# LEDCube.net
KiCad netlist of a schematic drawn in Altium Designer
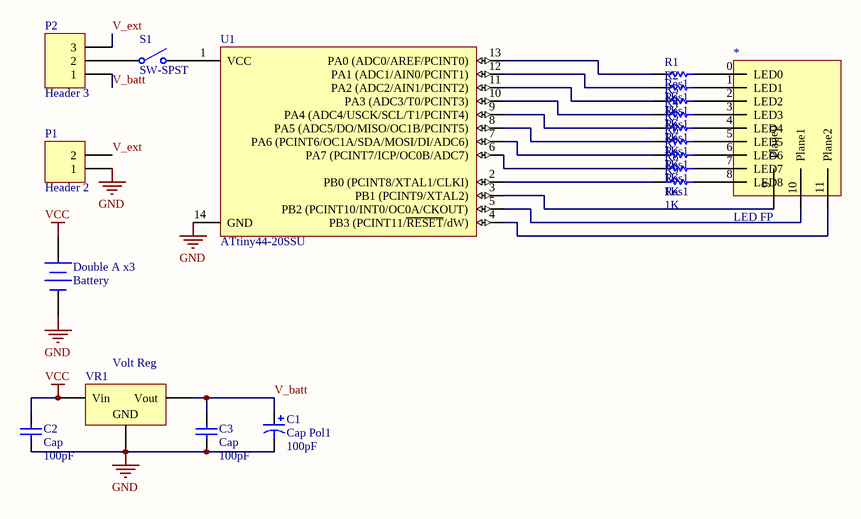
[diagram p0: LEDCube.SchDoc]

(export (version "E")
  (design (tool "Eeschema 10.0.6"))
  (components
    (comp (ref "*")
      (value "LED FP")
      (footprint "Cube Column FP")
      (libsource (lib "LEDFPSch") (part "LED FP"))
    )
    (comp (ref "C1")
      (value "Cap Pol1")
      (footprint "RB7.6-15")
      (description "Polarized Capacitor (Radial)")
      (fields (field (name "ALTIUM_VALUE") "100pF") (field (name "PUBLISHER") "Altium Limited"))
      (libsource (lib "Miscellaneous Devices") (part "Cap Pol1"))
    )
    (comp (ref "C2")
      (value "Cap")
      (footprint "RAD-0.3")
      (description "Capacitor")
      (fields (field (name "ALTIUM_VALUE") "100pF") (field (name "PUBLISHER") "Altium Limited"))
      (libsource (lib "Miscellaneous Devices") (part "Cap"))
    )
    (comp (ref "C3")
      (value "Cap")
      (footprint "RAD-0.3")
      (description "Capacitor")
      (fields (field (name "ALTIUM_VALUE") "100pF") (field (name "PUBLISHER") "Altium Limited"))
      (libsource (lib "Miscellaneous Devices") (part "Cap"))
    )
    (comp (ref "Double A x3")
      (value "Battery")
      (footprint "BAT-2")
      (description "Multicell Battery")
      (fields (field (name "PUBLISHER") "Altium Limited"))
      (libsource (lib "Miscellaneous Devices") (part "Battery"))
    )
    (comp (ref "P1")
      (value "Header 2")
      (footprint "HDR1X2")
      (description "Header, 2-Pin")
      (fields (field (name "PUBLISHER") "Altium Limited"))
      (libsource (lib "Miscellaneous Connectors") (part "Header 2"))
    )
    (comp (ref "P2")
      (value "Header 3")
      (footprint "HDR1X3")
      (description "Header, 3-Pin")
      (fields (field (name "PUBLISHER") "Altium Limited"))
      (libsource (lib "Miscellaneous Connectors") (part "Header 3"))
    )
    (comp (ref "R1")
      (value "Res1")
      (footprint "AXIAL-0.3")
      (description "Resistor")
      (fields (field (name "ALTIUM_VALUE") "1K") (field (name "PUBLISHER") "Altium Limited"))
      (libsource (lib "Miscellaneous Devices") (part "Res1"))
    )
    (comp (ref "R2")
      (value "Res1")
      (footprint "AXIAL-0.3")
      (description "Resistor")
      (fields (field (name "ALTIUM_VALUE") "1K") (field (name "PUBLISHER") "Altium Limited"))
      (libsource (lib "Miscellaneous Devices") (part "Res1"))
    )
    (comp (ref "R3")
      (value "Res1")
      (footprint "AXIAL-0.3")
      (description "Resistor")
      (fields (field (name "ALTIUM_VALUE") "1K") (field (name "PUBLISHER") "Altium Limited"))
      (libsource (lib "Miscellaneous Devices") (part "Res1"))
    )
    (comp (ref "R4")
      (value "Res1")
      (footprint "AXIAL-0.3")
      (description "Resistor")
      (fields (field (name "ALTIUM_VALUE") "1K") (field (name "PUBLISHER") "Altium Limited"))
      (libsource (lib "Miscellaneous Devices") (part "Res1"))
    )
    (comp (ref "R5")
      (value "Res1")
      (footprint "AXIAL-0.3")
      (description "Resistor")
      (fields (field (name "ALTIUM_VALUE") "1K") (field (name "PUBLISHER") "Altium Limited"))
      (libsource (lib "Miscellaneous Devices") (part "Res1"))
    )
    (comp (ref "R6")
      (value "Res1")
      (footprint "AXIAL-0.3")
      (description "Resistor")
      (fields (field (name "ALTIUM_VALUE") "1K") (field (name "PUBLISHER") "Altium Limited"))
      (libsource (lib "Miscellaneous Devices") (part "Res1"))
    )
    (comp (ref "R7")
      (value "Res1")
      (footprint "AXIAL-0.3")
      (description "Resistor")
      (fields (field (name "ALTIUM_VALUE") "1K") (field (name "PUBLISHER") "Altium Limited"))
      (libsource (lib "Miscellaneous Devices") (part "Res1"))
    )
    (comp (ref "R8")
      (value "Res1")
      (footprint "AXIAL-0.3")
      (description "Resistor")
      (fields (field (name "ALTIUM_VALUE") "1K") (field (name "PUBLISHER") "Altium Limited"))
      (libsource (lib "Miscellaneous Devices") (part "Res1"))
    )
    (comp (ref "R9")
      (value "Res1")
      (footprint "AXIAL-0.3")
      (description "Resistor")
      (fields (field (name "ALTIUM_VALUE") "1K") (field (name "PUBLISHER") "Altium Limited"))
      (libsource (lib "Miscellaneous Devices") (part "Res1"))
    )
    (comp (ref "S1")
      (value "SW-SPST")
      (footprint "SPST-2")
      (description "Single-Pole, Single-Throw Switch")
      (fields (field (name "PUBLISHER") "Altium Limited"))
      (libsource (lib "Miscellaneous Devices") (part "SW-SPST"))
    )
    (comp (ref "U1")
      (value "ATtiny44-20SSU")
      (footprint "14S1_N")
      (fields (field (name "PUBLISHER") "Altium Limited"))
      (libsource (lib "Atmel Microcontroller 8-Bit tinyAVR") (part "ATtiny44-20SSU"))
    )
    (comp (ref "VR1")
      (value "Volt Reg")
      (footprint "D2PAK_N")
      (description "Voltage Regulator")
      (fields (field (name "PUBLISHER") "Altium Limited"))
      (libsource (lib "Miscellaneous Devices") (part "Volt Reg"))
    )
  )
  (nets
    (net (code "1") (name "/V_batt") (class "Default")
      (node (ref "C1") (pin "1") (pinfunction "1_1") (pintype "passive"))
      (node (ref "C3") (pin "2") (pinfunction "2_2") (pintype "passive"))
      (node (ref "P2") (pin "1") (pinfunction "1_1") (pintype "passive"))
      (node (ref "VR1") (pin "3") (pinfunction "Vout_3") (pintype "passive"))
    )
    (net (code "2") (name "/V_ext") (class "Default")
      (node (ref "P1") (pin "2") (pinfunction "2_2") (pintype "passive"))
      (node (ref "P2") (pin "3") (pinfunction "3_3") (pintype "passive"))
    )
    (net (code "3") (name "GND") (class "Default")
      (node (ref "C1") (pin "2") (pinfunction "2_2") (pintype "passive"))
      (node (ref "C2") (pin "1") (pinfunction "1_1") (pintype "passive"))
      (node (ref "C3") (pin "1") (pinfunction "1_1") (pintype "passive"))
      (node (ref "Double A x3") (pin "2") (pinfunction "-_2") (pintype "passive"))
      (node (ref "P1") (pin "1") (pinfunction "1_1") (pintype "passive"))
      (node (ref "U1") (pin "14") (pinfunction "GND_14") (pintype "power_in"))
      (node (ref "VR1") (pin "2") (pinfunction "GND_2") (pintype "passive"))
    )
    (net (code "4") (name "Net-(*-LED0)") (class "Default")
      (node (ref "*") (pin "0") (pinfunction "LED0_0") (pintype "passive"))
      (node (ref "R1") (pin "2") (pinfunction "2_2") (pintype "passive"))
    )
    (net (code "5") (name "Net-(*-LED1)") (class "Default")
      (node (ref "*") (pin "1") (pinfunction "LED1_1") (pintype "passive"))
      (node (ref "R2") (pin "2") (pinfunction "2_2") (pintype "passive"))
    )
    (net (code "6") (name "Net-(*-LED2)") (class "Default")
      (node (ref "*") (pin "2") (pinfunction "LED2_2") (pintype "passive"))
      (node (ref "R3") (pin "2") (pinfunction "2_2") (pintype "passive"))
    )
    (net (code "7") (name "Net-(*-LED3)") (class "Default")
      (node (ref "*") (pin "3") (pinfunction "LED3_3") (pintype "passive"))
      (node (ref "R4") (pin "2") (pinfunction "2_2") (pintype "passive"))
    )
    (net (code "8") (name "Net-(*-LED4)") (class "Default")
      (node (ref "*") (pin "4") (pinfunction "LED4_4") (pintype "passive"))
      (node (ref "R5") (pin "2") (pinfunction "2_2") (pintype "passive"))
    )
    (net (code "9") (name "Net-(*-LED5)") (class "Default")
      (node (ref "*") (pin "5") (pinfunction "LED5_5") (pintype "passive"))
      (node (ref "R6") (pin "2") (pinfunction "2_2") (pintype "passive"))
    )
    (net (code "10") (name "Net-(*-LED6)") (class "Default")
      (node (ref "*") (pin "6") (pinfunction "LED6_6") (pintype "passive"))
      (node (ref "R7") (pin "2") (pinfunction "2_2") (pintype "passive"))
    )
    (net (code "11") (name "Net-(*-LED7)") (class "Default")
      (node (ref "*") (pin "7") (pinfunction "LED7_7") (pintype "passive"))
      (node (ref "R8") (pin "2") (pinfunction "2_2") (pintype "passive"))
    )
    (net (code "12") (name "Net-(*-LED8)") (class "Default")
      (node (ref "*") (pin "8") (pinfunction "LED8_8") (pintype "passive"))
      (node (ref "R9") (pin "2") (pinfunction "2_2") (pintype "passive"))
    )
    (net (code "13") (name "Net-(*-Plane0)") (class "Default")
      (node (ref "*") (pin "9") (pinfunction "Plane0_9") (pintype "passive"))
      (node (ref "U1") (pin "3") (pinfunction "PB1_(PCINT9/XTAL2)_3") (pintype "bidirectional"))
    )
    (net (code "14") (name "Net-(*-Plane1)") (class "Default")
      (node (ref "*") (pin "10") (pinfunction "Plane1_10") (pintype "passive"))
      (node (ref "U1") (pin "5") (pinfunction "PB2_(PCINT10/INT0/OC0A/CKOUT)_5") (pintype "bidirectional"))
    )
    (net (code "15") (name "Net-(*-Plane2)") (class "Default")
      (node (ref "*") (pin "11") (pinfunction "Plane2_11") (pintype "passive"))
      (node (ref "U1") (pin "4") (pinfunction "PB3_(PCINT11/~{RESET}/dW)_4") (pintype "bidirectional"))
    )
    (net (code "16") (name "Net-(S1-COMMON)") (class "Default")
      (node (ref "P2") (pin "2") (pinfunction "2_2") (pintype "passive"))
      (node (ref "S1") (pin "1") (pinfunction "COMMON_1") (pintype "passive"))
    )
    (net (code "17") (name "Net-(S1-NO)") (class "Default")
      (node (ref "S1") (pin "2") (pinfunction "NO_2") (pintype "passive"))
      (node (ref "U1") (pin "1") (pinfunction "VCC_1") (pintype "power_in"))
    )
    (net (code "18") (name "Net-(U1-PA0_(ADC0{slash}AREF{slash}PCINT0))") (class "Default")
      (node (ref "R1") (pin "1") (pinfunction "1_1") (pintype "passive"))
      (node (ref "U1") (pin "13") (pinfunction "PA0_(ADC0/AREF/PCINT0)_13") (pintype "bidirectional"))
    )
    (net (code "19") (name "Net-(U1-PA1_(ADC1{slash}AIN0{slash}PCINT1))") (class "Default")
      (node (ref "R2") (pin "1") (pinfunction "1_1") (pintype "passive"))
      (node (ref "U1") (pin "12") (pinfunction "PA1_(ADC1/AIN0/PCINT1)_12") (pintype "bidirectional"))
    )
    (net (code "20") (name "Net-(U1-PA2_(ADC2{slash}AIN1{slash}PCINT2))") (class "Default")
      (node (ref "R3") (pin "1") (pinfunction "1_1") (pintype "passive"))
      (node (ref "U1") (pin "11") (pinfunction "PA2_(ADC2/AIN1/PCINT2)_11") (pintype "bidirectional"))
    )
    (net (code "21") (name "Net-(U1-PA3_(ADC3{slash}T0{slash}PCINT3))") (class "Default")
      (node (ref "R4") (pin "1") (pinfunction "1_1") (pintype "passive"))
      (node (ref "U1") (pin "10") (pinfunction "PA3_(ADC3/T0/PCINT3)_10") (pintype "bidirectional"))
    )
    (net (code "22") (name "Net-(U1-PA4_(ADC4{slash}USCK{slash}SCL{slash}T1{slash}PCINT4))") (class "Default")
      (node (ref "R5") (pin "1") (pinfunction "1_1") (pintype "passive"))
      (node (ref "U1") (pin "9") (pinfunction "PA4_(ADC4/USCK/SCL/T1/PCINT4)_9") (pintype "bidirectional"))
    )
    (net (code "23") (name "Net-(U1-PA5_(ADC5{slash}DO{slash}MISO{slash}OC1B{slash}PCINT5))") (class "Default")
      (node (ref "R6") (pin "1") (pinfunction "1_1") (pintype "passive"))
      (node (ref "U1") (pin "8") (pinfunction "PA5_(ADC5/DO/MISO/OC1B/PCINT5)_8") (pintype "bidirectional"))
    )
    (net (code "24") (name "Net-(U1-PA6_(PCINT6{slash}OC1A{slash}SDA{slash}MOSI{slash}DI{slash}ADC6))") (class "Default")
      (node (ref "R7") (pin "1") (pinfunction "1_1") (pintype "passive"))
      (node (ref "U1") (pin "7") (pinfunction "PA6_(PCINT6/OC1A/SDA/MOSI/DI/ADC6)_7") (pintype "bidirectional"))
    )
    (net (code "25") (name "Net-(U1-PA7_(PCINT7{slash}ICP{slash}OC0B{slash}ADC7))") (class "Default")
      (node (ref "R8") (pin "1") (pinfunction "1_1") (pintype "passive"))
      (node (ref "U1") (pin "6") (pinfunction "PA7_(PCINT7/ICP/OC0B/ADC7)_6") (pintype "bidirectional"))
    )
    (net (code "26") (name "Net-(U1-PB0_(PCINT8{slash}XTAL1{slash}CLKI))") (class "Default")
      (node (ref "R9") (pin "1") (pinfunction "1_1") (pintype "passive"))
      (node (ref "U1") (pin "2") (pinfunction "PB0_(PCINT8/XTAL1/CLKI)_2") (pintype "bidirectional"))
    )
    (net (code "27") (name "VCC") (class "Default")
      (node (ref "C2") (pin "2") (pinfunction "2_2") (pintype "passive"))
      (node (ref "Double A x3") (pin "1") (pinfunction "+_1") (pintype "passive"))
      (node (ref "VR1") (pin "1") (pinfunction "Vin_1") (pintype "passive"))
    )
  )
)
